# 14-GPS.net
KiCad netlist of a schematic drawn in Altium Designer
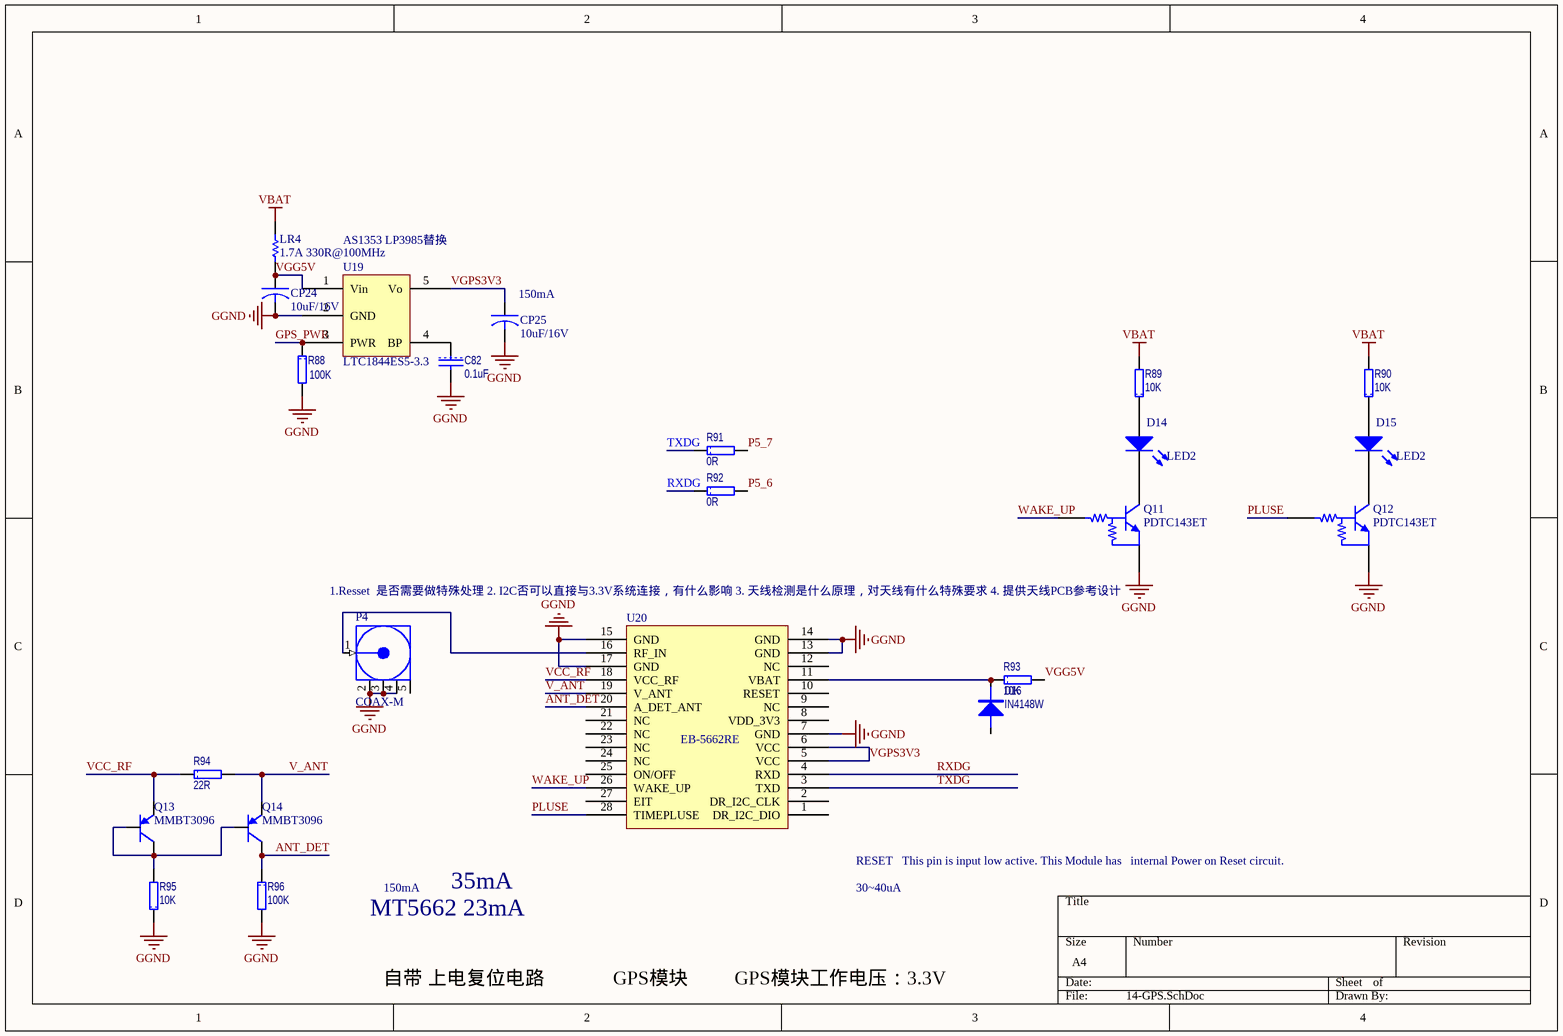
[diagram p0: 14-GPS.SchDoc]

(export (version "E")
  (design (tool "Eeschema 10.0.6"))
  (components
    (comp (ref "C82")
      (value "0.1uF")
      (footprint "1608[0603]")
      (description "Capacitor")
      (fields (field (name "MANUFACTURER") "TDK"))
      (libsource (lib "*") (part "CAP"))
    )
    (comp (ref "CP24")
      (value "10uF/16V")
      (footprint "3216[1206]")
      (description "Tantalum Capacitor")
      (libsource (lib "*") (part "CAPACITOR"))
    )
    (comp (ref "CP25")
      (value "10uF/16V")
      (footprint "3216[1206]")
      (description "Tantalum Capacitor")
      (libsource (lib "*") (part "CAPACITOR"))
    )
    (comp (ref "D14")
      (value "LED2")
      (footprint "0805LED")
      (description "Typical RED, GREEN, YELLOW, AMBER GaAs LED")
      (fields (field (name "PUBLISHER") "Altium Limited"))
      (libsource (lib "Miscellaneous Devices") (part "LED2"))
    )
    (comp (ref "D15")
      (value "LED2")
      (footprint "0805LED")
      (description "Typical RED, GREEN, YELLOW, AMBER GaAs LED")
      (fields (field (name "PUBLISHER") "Altium Limited"))
      (libsource (lib "Miscellaneous Devices") (part "LED2"))
    )
    (comp (ref "D16")
      (value "IN4148W")
      (footprint "SOD123")
      (description "DIODE")
      (libsource (lib "*") (part "DIODE"))
    )
    (comp (ref "LR4")
      (value "1.7A 330R@100MHz")
      (footprint "1608[0603]RV")
      (description "Semiconductor Resistor")
      (fields (field (name "Comment") "MPZ1608S331A") (field (name "PUBLISHER") "Altium Limited"))
      (libsource (lib "Miscellaneous Devices") (part "Res Semi"))
    )
    (comp (ref "P4")
      (value "COAX-M")
      (footprint "MHF[MCB3]-V4")
      (description "RF Coaxial PCB Connector, MMCX; Thru-Hole, Vertical Mount Plug,  50 Ohm Impedance")
      (fields (field (name "PUBLISHER") "Altium Limited"))
      (libsource (lib "Miscellaneous Connectors") (part "COAX-M"))
    )
    (comp (ref "Q11")
      (value "PDTC143ET")
      (footprint "SOT23_N")
      (description "NPN Resistor-equipped Transistor")
      (fields (field (name "PUBLISHER") "Altium Limited"))
      (libsource (lib "Philips Discrete BJT - Low Power") (part "PDTC143ET"))
    )
    (comp (ref "Q12")
      (value "PDTC143ET")
      (footprint "SOT23_N")
      (description "NPN Resistor-equipped Transistor")
      (fields (field (name "PUBLISHER") "Altium Limited"))
      (libsource (lib "Philips Discrete BJT - Low Power") (part "PDTC143ET"))
    )
    (comp (ref "Q13")
      (value "MMBT3096")
      (footprint "SOT23_N")
      (description "三极管")
      (libsource (lib "*") (part "MMBT3096"))
    )
    (comp (ref "Q14")
      (value "MMBT3096")
      (footprint "SOT23_N")
      (description "三极管")
      (libsource (lib "*") (part "MMBT3096"))
    )
    (comp (ref "R88")
      (value "100K")
      (footprint "1608[0603]R")
      (description "RES")
      (libsource (lib "*") (part "RES"))
    )
    (comp (ref "R89")
      (value "10K")
      (footprint "1608[0603]R")
      (description "RES")
      (libsource (lib "*") (part "RES"))
    )
    (comp (ref "R90")
      (value "10K")
      (footprint "1608[0603]R")
      (description "RES")
      (libsource (lib "*") (part "RES"))
    )
    (comp (ref "R91")
      (value "0R")
      (footprint "1608[0603]R")
      (description "RES")
      (libsource (lib "*") (part "RES"))
    )
    (comp (ref "R92")
      (value "0R")
      (footprint "1608[0603]R")
      (description "RES")
      (libsource (lib "*") (part "RES"))
    )
    (comp (ref "R93")
      (value "10K")
      (footprint "1608[0603]R")
      (description "RES")
      (libsource (lib "*") (part "RES"))
    )
    (comp (ref "R94")
      (value "22R")
      (footprint "1608[0603]R")
      (description "RES")
      (libsource (lib "*") (part "RES"))
    )
    (comp (ref "R95")
      (value "10K")
      (footprint "1608[0603]R")
      (description "RES")
      (libsource (lib "*") (part "RES"))
    )
    (comp (ref "R96")
      (value "100K")
      (footprint "1608[0603]R")
      (description "RES")
      (libsource (lib "*") (part "RES"))
    )
    (comp (ref "U19")
      (value "LTC1844ES5-3.3")
      (footprint "SOT23-5BN")
      (description "电源管理")
      (libsource (lib "S3C2440V9") (part "LT1761"))
    )
    (comp (ref "U20")
      (value "EB-5662RE")
      (footprint "EB-5662RE")
      (description "GPS模块")
      (libsource (lib "*") (part "EB-5662RE"))
    )
  )
  (nets
    (net (code "1") (name "/ANT_DET") (class "Default")
      (node (ref "Q14") (pin "3") (pinfunction "3_3") (pintype "passive"))
      (node (ref "R96") (pin "1") (pinfunction "1_1") (pintype "passive"))
      (node (ref "U20") (pin "20") (pinfunction "A_DET_ANT_20") (pintype "passive"))
    )
    (net (code "2") (name "/GPS_PWR") (class "Default")
      (node (ref "R88") (pin "1") (pinfunction "1_1") (pintype "passive"))
      (node (ref "U19") (pin "3") (pinfunction "PWR_3") (pintype "passive"))
    )
    (net (code "3") (name "/P5_6") (class "Default")
      (node (ref "R92") (pin "2") (pinfunction "2_2") (pintype "passive"))
    )
    (net (code "4") (name "/P5_7") (class "Default")
      (node (ref "R91") (pin "2") (pinfunction "2_2") (pintype "passive"))
    )
    (net (code "5") (name "/PLUSE") (class "Default")
      (node (ref "Q12") (pin "1") (pinfunction "B_1") (pintype "passive"))
      (node (ref "U20") (pin "28") (pinfunction "TIMEPLUSE_28") (pintype "passive"))
    )
    (net (code "6") (name "/RXDG") (class "Default")
      (node (ref "R92") (pin "1") (pinfunction "1_1") (pintype "passive"))
      (node (ref "U20") (pin "4") (pinfunction "RXD_4") (pintype "passive"))
    )
    (net (code "7") (name "/TXDG") (class "Default")
      (node (ref "R91") (pin "1") (pinfunction "1_1") (pintype "passive"))
      (node (ref "U20") (pin "3") (pinfunction "TXD_3") (pintype "passive"))
    )
    (net (code "8") (name "/VCC_RF") (class "Default")
      (node (ref "Q13") (pin "2") (pinfunction "2_2") (pintype "passive"))
      (node (ref "R94") (pin "1") (pinfunction "1_1") (pintype "passive"))
      (node (ref "U20") (pin "18") (pinfunction "VCC_RF_18") (pintype "passive"))
    )
    (net (code "9") (name "/VGG5V") (class "Default")
      (node (ref "CP24") (pin "1") (pinfunction "1_1") (pintype "passive"))
      (node (ref "LR4") (pin "1") (pinfunction "1_1") (pintype "passive"))
      (node (ref "R93") (pin "2") (pinfunction "2_2") (pintype "passive"))
      (node (ref "U19") (pin "1") (pinfunction "Vin_1") (pintype "passive"))
    )
    (net (code "10") (name "/VGPS3V3") (class "Default")
      (node (ref "CP25") (pin "1") (pinfunction "1_1") (pintype "passive"))
      (node (ref "U19") (pin "5") (pinfunction "Vo_5") (pintype "passive"))
      (node (ref "U20") (pin "5") (pinfunction "VCC_5") (pintype "passive"))
      (node (ref "U20") (pin "6") (pinfunction "VCC_6") (pintype "passive"))
    )
    (net (code "11") (name "/V_ANT") (class "Default")
      (node (ref "Q14") (pin "2") (pinfunction "2_2") (pintype "passive"))
      (node (ref "R94") (pin "2") (pinfunction "2_2") (pintype "passive"))
      (node (ref "U20") (pin "19") (pinfunction "V_ANT_19") (pintype "passive"))
    )
    (net (code "12") (name "/WAKE_UP") (class "Default")
      (node (ref "Q11") (pin "1") (pinfunction "B_1") (pintype "passive"))
      (node (ref "U20") (pin "26") (pinfunction "WAKE_UP_26") (pintype "passive"))
    )
    (net (code "13") (name "GGND") (class "Default")
      (node (ref "C82") (pin "2") (pinfunction "2_2") (pintype "passive"))
      (node (ref "CP24") (pin "2") (pinfunction "2_2") (pintype "passive"))
      (node (ref "CP25") (pin "2") (pinfunction "2_2") (pintype "passive"))
      (node (ref "P4") (pin "2") (pinfunction "GND_2") (pintype "power_in"))
      (node (ref "P4") (pin "3") (pinfunction "GND_3") (pintype "power_in"))
      (node (ref "P4") (pin "4") (pinfunction "GND_4") (pintype "power_in"))
      (node (ref "Q11") (pin "2") (pinfunction "E_2") (pintype "passive"))
      (node (ref "Q12") (pin "2") (pinfunction "E_2") (pintype "passive"))
      (node (ref "R88") (pin "2") (pinfunction "2_2") (pintype "passive"))
      (node (ref "R95") (pin "1") (pinfunction "1_1") (pintype "passive"))
      (node (ref "R96") (pin "2") (pinfunction "2_2") (pintype "passive"))
      (node (ref "U19") (pin "2") (pinfunction "GND_2") (pintype "passive"))
      (node (ref "U20") (pin "13") (pinfunction "GND_13") (pintype "passive"))
      (node (ref "U20") (pin "14") (pinfunction "GND_14") (pintype "passive"))
      (node (ref "U20") (pin "15") (pinfunction "GND_15") (pintype "passive"))
      (node (ref "U20") (pin "17") (pinfunction "GND_17") (pintype "passive"))
      (node (ref "U20") (pin "7") (pinfunction "GND_7") (pintype "passive"))
    )
    (net (code "14") (name "Net-(D14-A)") (class "Default")
      (node (ref "D14") (pin "1") (pinfunction "A_1") (pintype "passive"))
      (node (ref "R89") (pin "1") (pinfunction "1_1") (pintype "passive"))
    )
    (net (code "15") (name "Net-(D14-K)") (class "Default")
      (node (ref "D14") (pin "2") (pinfunction "K_2") (pintype "passive"))
      (node (ref "Q11") (pin "3") (pinfunction "C_3") (pintype "passive"))
    )
    (net (code "16") (name "Net-(D15-A)") (class "Default")
      (node (ref "D15") (pin "1") (pinfunction "A_1") (pintype "passive"))
      (node (ref "R90") (pin "1") (pinfunction "1_1") (pintype "passive"))
    )
    (net (code "17") (name "Net-(D15-K)") (class "Default")
      (node (ref "D15") (pin "2") (pinfunction "K_2") (pintype "passive"))
      (node (ref "Q12") (pin "3") (pinfunction "C_3") (pintype "passive"))
    )
    (net (code "18") (name "Net-(P4-Signal)") (class "Default")
      (node (ref "P4") (pin "1") (pinfunction "Signal_1") (pintype "input"))
      (node (ref "U20") (pin "16") (pinfunction "RF_IN_16") (pintype "passive"))
    )
    (net (code "19") (name "Net-(Q13-Pad1)") (class "Default")
      (node (ref "Q13") (pin "1") (pinfunction "1_1") (pintype "passive"))
      (node (ref "Q13") (pin "3") (pinfunction "3_3") (pintype "passive"))
      (node (ref "Q14") (pin "1") (pinfunction "1_1") (pintype "passive"))
      (node (ref "R95") (pin "2") (pinfunction "2_2") (pintype "passive"))
    )
    (net (code "20") (name "Net-(U19-BP)") (class "Default")
      (node (ref "C82") (pin "1") (pinfunction "1_1") (pintype "passive"))
      (node (ref "U19") (pin "4") (pinfunction "BP_4") (pintype "passive"))
    )
    (net (code "21") (name "Net-(U20-VBAT)") (class "Default")
      (node (ref "D16") (pin "2") (pinfunction "2_2") (pintype "passive"))
      (node (ref "R93") (pin "1") (pinfunction "1_1") (pintype "passive"))
      (node (ref "U20") (pin "11") (pinfunction "VBAT_11") (pintype "passive"))
    )
    (net (code "22") (name "VBAT") (class "Default")
      (node (ref "LR4") (pin "2") (pinfunction "2_2") (pintype "passive"))
      (node (ref "R89") (pin "2") (pinfunction "2_2") (pintype "passive"))
      (node (ref "R90") (pin "2") (pinfunction "2_2") (pintype "passive"))
    )
    (net (code "23") (name "unconnected-(D16-Pad1)") (class "Default")
      (node (ref "D16") (pin "1") (pinfunction "1_1") (pintype "passive"))
    )
    (net (code "24") (name "unconnected-(P4-GND-Pad5)") (class "Default")
      (node (ref "P4") (pin "5") (pinfunction "GND_5") (pintype "power_in"))
    )
    (net (code "25") (name "unconnected-(U20-DR_I2C_CLK-Pad2)") (class "Default")
      (node (ref "U20") (pin "2") (pinfunction "DR_I2C_CLK_2") (pintype "passive"))
    )
    (net (code "26") (name "unconnected-(U20-DR_I2C_DIO-Pad1)") (class "Default")
      (node (ref "U20") (pin "1") (pinfunction "DR_I2C_DIO_1") (pintype "passive"))
    )
    (net (code "27") (name "unconnected-(U20-EIT-Pad27)") (class "Default")
      (node (ref "U20") (pin "27") (pinfunction "EIT_27") (pintype "passive"))
    )
    (net (code "28") (name "unconnected-(U20-NC-Pad9)") (class "Default")
      (node (ref "U20") (pin "9") (pinfunction "NC_9") (pintype "passive"))
    )
    (net (code "29") (name "unconnected-(U20-NC-Pad12)") (class "Default")
      (node (ref "U20") (pin "12") (pinfunction "NC_12") (pintype "passive"))
    )
    (net (code "30") (name "unconnected-(U20-NC-Pad21)") (class "Default")
      (node (ref "U20") (pin "21") (pinfunction "NC_21") (pintype "passive"))
    )
    (net (code "31") (name "unconnected-(U20-NC-Pad22)") (class "Default")
      (node (ref "U20") (pin "22") (pinfunction "NC_22") (pintype "passive"))
    )
    (net (code "32") (name "unconnected-(U20-NC-Pad23)") (class "Default")
      (node (ref "U20") (pin "23") (pinfunction "NC_23") (pintype "passive"))
    )
    (net (code "33") (name "unconnected-(U20-NC-Pad24)") (class "Default")
      (node (ref "U20") (pin "24") (pinfunction "NC_24") (pintype "passive"))
    )
    (net (code "34") (name "unconnected-(U20-ON{slash}OFF-Pad25)") (class "Default")
      (node (ref "U20") (pin "25") (pinfunction "ON/OFF_25") (pintype "passive"))
    )
    (net (code "35") (name "unconnected-(U20-RESET-Pad10)") (class "Default")
      (node (ref "U20") (pin "10") (pinfunction "RESET_10") (pintype "passive"))
    )
    (net (code "36") (name "unconnected-(U20-VDD_3V3-Pad8)") (class "Default")
      (node (ref "U20") (pin "8") (pinfunction "VDD_3V3_8") (pintype "passive"))
    )
  )
)
